# left_revision0_6.net
KiCad netlist of a schematic drawn in EAGLE
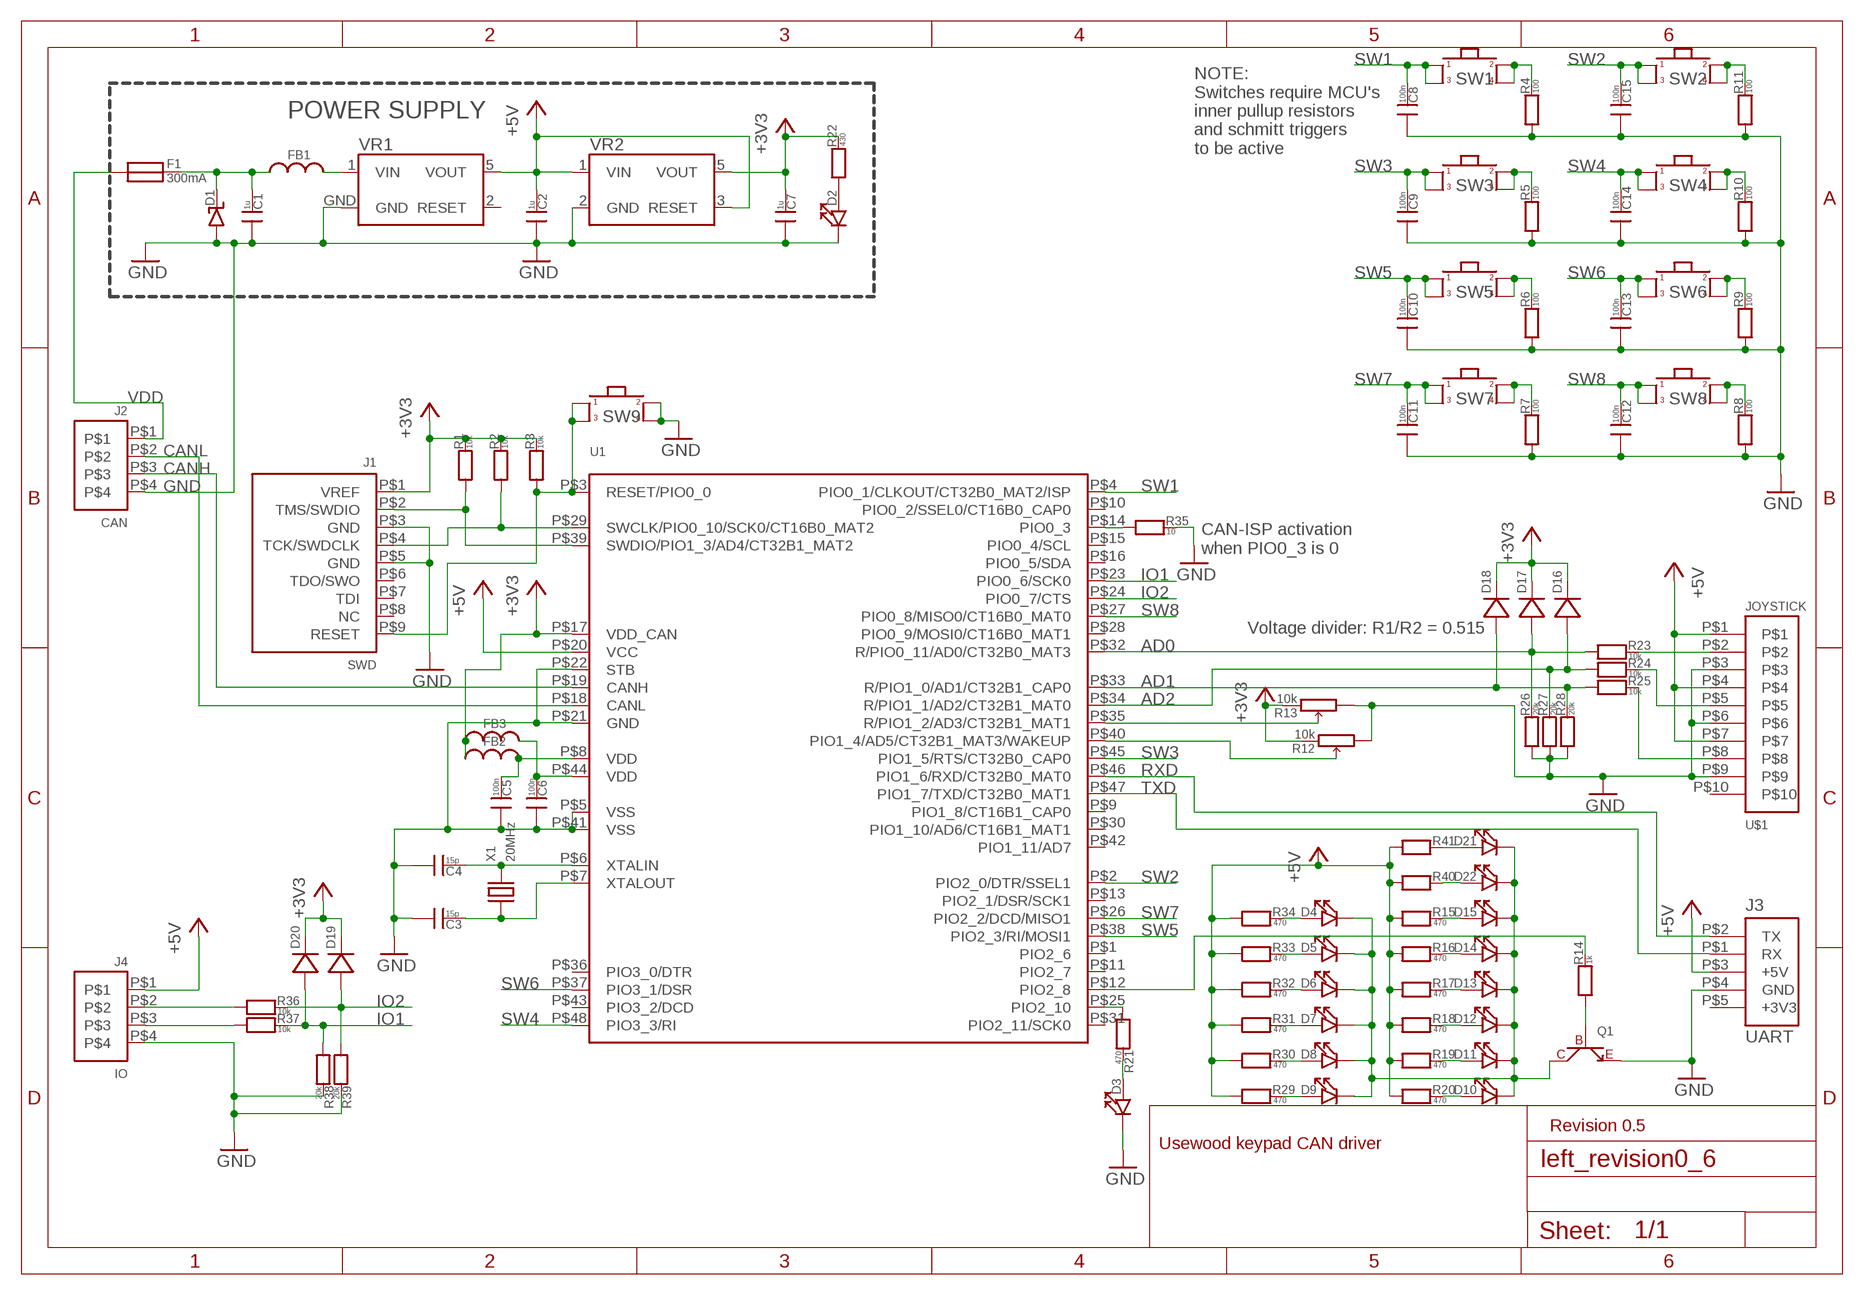
[diagram p0: schematic, sheet 1]

(export (version "E")
  (design (tool "Eeschema 10.0.6"))
  (components
    (comp (ref "C1")
      (value "1u")
      (footprint "eagle-import:0603")
      (libsource (lib "eagle-import") (part "CAP0603"))
    )
    (comp (ref "C2")
      (value "1u")
      (footprint "eagle-import:0603")
      (libsource (lib "eagle-import") (part "CAP0603"))
    )
    (comp (ref "C3")
      (value "15p")
      (footprint "eagle-import:0603")
      (libsource (lib "eagle-import") (part "CAP0603"))
    )
    (comp (ref "C4")
      (value "15p")
      (footprint "eagle-import:0603")
      (libsource (lib "eagle-import") (part "CAP0603"))
    )
    (comp (ref "C5")
      (value "100n")
      (footprint "eagle-import:0603")
      (libsource (lib "eagle-import") (part "CAP0603"))
    )
    (comp (ref "C6")
      (value "100n")
      (footprint "eagle-import:0603")
      (libsource (lib "eagle-import") (part "CAP0603"))
    )
    (comp (ref "C7")
      (value "1u")
      (footprint "eagle-import:0603")
      (libsource (lib "eagle-import") (part "CAP0603"))
    )
    (comp (ref "C8")
      (value "100n")
      (footprint "eagle-import:0603")
      (libsource (lib "eagle-import") (part "CAP0603"))
    )
    (comp (ref "C9")
      (value "100n")
      (footprint "eagle-import:0603")
      (libsource (lib "eagle-import") (part "CAP0603"))
    )
    (comp (ref "C10")
      (value "100n")
      (footprint "eagle-import:0603")
      (libsource (lib "eagle-import") (part "CAP0603"))
    )
    (comp (ref "C11")
      (value "100n")
      (footprint "eagle-import:0603")
      (libsource (lib "eagle-import") (part "CAP0603"))
    )
    (comp (ref "C12")
      (value "100n")
      (footprint "eagle-import:0603")
      (libsource (lib "eagle-import") (part "CAP0603"))
    )
    (comp (ref "C13")
      (value "100n")
      (footprint "eagle-import:0603")
      (libsource (lib "eagle-import") (part "CAP0603"))
    )
    (comp (ref "C14")
      (value "100n")
      (footprint "eagle-import:0603")
      (libsource (lib "eagle-import") (part "CAP0603"))
    )
    (comp (ref "C15")
      (value "100n")
      (footprint "eagle-import:0603")
      (libsource (lib "eagle-import") (part "CAP0603"))
    )
    (comp (ref "D1")
      (value "DIODE_TVSDO-214AA")
      (footprint "eagle-import:DO-214AB")
      (libsource (lib "eagle-import") (part "DIODE_TVSDO-214AA"))
    )
    (comp (ref "D2")
      (value "LED0603")
      (footprint "eagle-import:0603")
      (libsource (lib "eagle-import") (part "LED0603"))
    )
    (comp (ref "D3")
      (value "LED0603")
      (footprint "eagle-import:0603")
      (libsource (lib "eagle-import") (part "LED0603"))
    )
    (comp (ref "D4")
      (value "LED0603")
      (footprint "eagle-import:0603")
      (libsource (lib "eagle-import") (part "LED0603"))
    )
    (comp (ref "D5")
      (value "LED0603")
      (footprint "eagle-import:0603")
      (libsource (lib "eagle-import") (part "LED0603"))
    )
    (comp (ref "D6")
      (value "LED0603")
      (footprint "eagle-import:0603")
      (libsource (lib "eagle-import") (part "LED0603"))
    )
    (comp (ref "D7")
      (value "LED0603")
      (footprint "eagle-import:0603")
      (libsource (lib "eagle-import") (part "LED0603"))
    )
    (comp (ref "D8")
      (value "LED0603")
      (footprint "eagle-import:0603")
      (libsource (lib "eagle-import") (part "LED0603"))
    )
    (comp (ref "D9")
      (value "LED0603")
      (footprint "eagle-import:0603")
      (libsource (lib "eagle-import") (part "LED0603"))
    )
    (comp (ref "D10")
      (value "LED0603")
      (footprint "eagle-import:0603")
      (libsource (lib "eagle-import") (part "LED0603"))
    )
    (comp (ref "D11")
      (value "LED0603")
      (footprint "eagle-import:0603")
      (libsource (lib "eagle-import") (part "LED0603"))
    )
    (comp (ref "D12")
      (value "LED0603")
      (footprint "eagle-import:0603")
      (libsource (lib "eagle-import") (part "LED0603"))
    )
    (comp (ref "D13")
      (value "LED0603")
      (footprint "eagle-import:0603")
      (libsource (lib "eagle-import") (part "LED0603"))
    )
    (comp (ref "D14")
      (value "LED0603")
      (footprint "eagle-import:0603")
      (libsource (lib "eagle-import") (part "LED0603"))
    )
    (comp (ref "D15")
      (value "LED0603")
      (footprint "eagle-import:0603")
      (libsource (lib "eagle-import") (part "LED0603"))
    )
    (comp (ref "D16")
      (value "DIODEDO219AB")
      (footprint "eagle-import:DO219AB")
      (libsource (lib "eagle-import") (part "DIODEDO219AB"))
    )
    (comp (ref "D17")
      (value "DIODEDO219AB")
      (footprint "eagle-import:DO219AB")
      (libsource (lib "eagle-import") (part "DIODEDO219AB"))
    )
    (comp (ref "D18")
      (value "DIODEDO219AB")
      (footprint "eagle-import:DO219AB")
      (libsource (lib "eagle-import") (part "DIODEDO219AB"))
    )
    (comp (ref "D19")
      (value "DIODEDO219AB")
      (footprint "eagle-import:DO219AB")
      (libsource (lib "eagle-import") (part "DIODEDO219AB"))
    )
    (comp (ref "D20")
      (value "DIODEDO219AB")
      (footprint "eagle-import:DO219AB")
      (libsource (lib "eagle-import") (part "DIODEDO219AB"))
    )
    (comp (ref "D21")
      (value "LED0603")
      (footprint "eagle-import:0603")
      (libsource (lib "eagle-import") (part "LED0603"))
    )
    (comp (ref "D22")
      (value "LED0603")
      (footprint "eagle-import:0603")
      (libsource (lib "eagle-import") (part "LED0603"))
    )
    (comp (ref "F1")
      (value "300mA")
      (footprint "eagle-import:FUSE_100MA")
      (libsource (lib "eagle-import") (part "FUSE100MA"))
    )
    (comp (ref "FB1")
      (value "FERRITE0603")
      (footprint "eagle-import:0603")
      (libsource (lib "eagle-import") (part "FERRITE0603"))
    )
    (comp (ref "FB2")
      (value "FERRITE0603")
      (footprint "eagle-import:0603")
      (libsource (lib "eagle-import") (part "FERRITE0603"))
    )
    (comp (ref "FB3")
      (value "FERRITE0603")
      (footprint "eagle-import:0603")
      (libsource (lib "eagle-import") (part "FERRITE0603"))
    )
    (comp (ref "J1")
      (value "SWD")
      (footprint "eagle-import:ARM_10_PIN_JTAG_SWD_CONNECTOR")
      (libsource (lib "eagle-import") (part "ARM_JTAG/SWD_HEADER_10_PINSMD"))
    )
    (comp (ref "J2")
      (value "CAN")
      (footprint "eagle-import:MOLEX_MICRO-FIT_4WAY")
      (libsource (lib "eagle-import") (part "MOLEX_MICRO-FIT_4WAYTH"))
    )
    (comp (ref "J3")
      (value "UART")
      (footprint "eagle-import:HEADER5_1")
      (libsource (lib "eagle-import") (part "HEADER_USARTTH"))
    )
    (comp (ref "J4")
      (value "IO")
      (footprint "eagle-import:MOLEX_MICRO-FIT_4WAY")
      (libsource (lib "eagle-import") (part "MOLEX_MICRO-FIT_4WAYTH"))
    )
    (comp (ref "Q1")
      (value "NPN_TRANSISTORSOT323")
      (footprint "eagle-import:SOT323")
      (libsource (lib "eagle-import") (part "NPN_TRANSISTORSOT323"))
    )
    (comp (ref "R1")
      (value "10k")
      (footprint "eagle-import:0603")
      (libsource (lib "eagle-import") (part "RES0603"))
    )
    (comp (ref "R2")
      (value "10k")
      (footprint "eagle-import:0603")
      (libsource (lib "eagle-import") (part "RES0603"))
    )
    (comp (ref "R3")
      (value "10k")
      (footprint "eagle-import:0603")
      (libsource (lib "eagle-import") (part "RES0603"))
    )
    (comp (ref "R4")
      (value "100")
      (footprint "eagle-import:0603")
      (libsource (lib "eagle-import") (part "RES0603"))
    )
    (comp (ref "R5")
      (value "100")
      (footprint "eagle-import:0603")
      (libsource (lib "eagle-import") (part "RES0603"))
    )
    (comp (ref "R6")
      (value "100")
      (footprint "eagle-import:0603")
      (libsource (lib "eagle-import") (part "RES0603"))
    )
    (comp (ref "R7")
      (value "100")
      (footprint "eagle-import:0603")
      (libsource (lib "eagle-import") (part "RES0603"))
    )
    (comp (ref "R8")
      (value "100")
      (footprint "eagle-import:0603")
      (libsource (lib "eagle-import") (part "RES0603"))
    )
    (comp (ref "R9")
      (value "100")
      (footprint "eagle-import:0603")
      (libsource (lib "eagle-import") (part "RES0603"))
    )
    (comp (ref "R10")
      (value "100")
      (footprint "eagle-import:0603")
      (libsource (lib "eagle-import") (part "RES0603"))
    )
    (comp (ref "R11")
      (value "100")
      (footprint "eagle-import:0603")
      (libsource (lib "eagle-import") (part "RES0603"))
    )
    (comp (ref "R12")
      (value "10k")
      (footprint "eagle-import:RES_POT_RK09K1130C94")
      (libsource (lib "eagle-import") (part "RES_POTRK09K1130C94"))
    )
    (comp (ref "R13")
      (value "10k")
      (footprint "eagle-import:RES_POT_RK09K1130C94")
      (libsource (lib "eagle-import") (part "RES_POTRK09K1130C94"))
    )
    (comp (ref "R14")
      (value "1k")
      (footprint "eagle-import:0603")
      (libsource (lib "eagle-import") (part "RES0603"))
    )
    (comp (ref "R15")
      (value "470")
      (footprint "eagle-import:0603")
      (libsource (lib "eagle-import") (part "RES0603"))
    )
    (comp (ref "R16")
      (value "470")
      (footprint "eagle-import:0603")
      (libsource (lib "eagle-import") (part "RES0603"))
    )
    (comp (ref "R17")
      (value "470")
      (footprint "eagle-import:0603")
      (libsource (lib "eagle-import") (part "RES0603"))
    )
    (comp (ref "R18")
      (value "470")
      (footprint "eagle-import:0603")
      (libsource (lib "eagle-import") (part "RES0603"))
    )
    (comp (ref "R19")
      (value "470")
      (footprint "eagle-import:0603")
      (libsource (lib "eagle-import") (part "RES0603"))
    )
    (comp (ref "R20")
      (value "470")
      (footprint "eagle-import:0603")
      (libsource (lib "eagle-import") (part "RES0603"))
    )
    (comp (ref "R21")
      (value "470")
      (footprint "eagle-import:0603")
      (libsource (lib "eagle-import") (part "RES0603"))
    )
    (comp (ref "R22")
      (value "430")
      (footprint "eagle-import:0603")
      (libsource (lib "eagle-import") (part "RES0603"))
    )
    (comp (ref "R23")
      (value "10k")
      (footprint "eagle-import:0603")
      (libsource (lib "eagle-import") (part "RES0603"))
    )
    (comp (ref "R24")
      (value "10k")
      (footprint "eagle-import:0603")
      (libsource (lib "eagle-import") (part "RES0603"))
    )
    (comp (ref "R25")
      (value "10k")
      (footprint "eagle-import:0603")
      (libsource (lib "eagle-import") (part "RES0603"))
    )
    (comp (ref "R26")
      (value "20k")
      (footprint "eagle-import:0603")
      (libsource (lib "eagle-import") (part "RES0603"))
    )
    (comp (ref "R27")
      (value "20k")
      (footprint "eagle-import:0603")
      (libsource (lib "eagle-import") (part "RES0603"))
    )
    (comp (ref "R28")
      (value "20k")
      (footprint "eagle-import:0603")
      (libsource (lib "eagle-import") (part "RES0603"))
    )
    (comp (ref "R29")
      (value "470")
      (footprint "eagle-import:0603")
      (libsource (lib "eagle-import") (part "RES0603"))
    )
    (comp (ref "R30")
      (value "470")
      (footprint "eagle-import:0603")
      (libsource (lib "eagle-import") (part "RES0603"))
    )
    (comp (ref "R31")
      (value "470")
      (footprint "eagle-import:0603")
      (libsource (lib "eagle-import") (part "RES0603"))
    )
    (comp (ref "R32")
      (value "470")
      (footprint "eagle-import:0603")
      (libsource (lib "eagle-import") (part "RES0603"))
    )
    (comp (ref "R33")
      (value "470")
      (footprint "eagle-import:0603")
      (libsource (lib "eagle-import") (part "RES0603"))
    )
    (comp (ref "R34")
      (value "470")
      (footprint "eagle-import:0603")
      (libsource (lib "eagle-import") (part "RES0603"))
    )
    (comp (ref "R35")
      (value "10")
      (footprint "eagle-import:0603")
      (libsource (lib "eagle-import") (part "RES0603"))
    )
    (comp (ref "R36")
      (value "10k")
      (footprint "eagle-import:0603")
      (libsource (lib "eagle-import") (part "RES0603"))
    )
    (comp (ref "R37")
      (value "10k")
      (footprint "eagle-import:0603")
      (libsource (lib "eagle-import") (part "RES0603"))
    )
    (comp (ref "R38")
      (value "20k")
      (footprint "eagle-import:0603")
      (libsource (lib "eagle-import") (part "RES0603"))
    )
    (comp (ref "R39")
      (value "20k")
      (footprint "eagle-import:0603")
      (libsource (lib "eagle-import") (part "RES0603"))
    )
    (comp (ref "R40")
      (value "RES0603")
      (footprint "eagle-import:0603")
      (libsource (lib "eagle-import") (part "RES0603"))
    )
    (comp (ref "R41")
      (value "RES0603")
      (footprint "eagle-import:0603")
      (libsource (lib "eagle-import") (part "RES0603"))
    )
    (comp (ref "SW1")
      (value "SWITCH12X12MM_CENTER_HOLE")
      (footprint "eagle-import:SWITCH_12X12MM_CENTER_HOLE")
      (libsource (lib "eagle-import") (part "SWITCH12X12MM_CENTER_HOLE"))
    )
    (comp (ref "SW2")
      (value "SWITCH12X12MM_CENTER_HOLE")
      (footprint "eagle-import:SWITCH_12X12MM_CENTER_HOLE")
      (libsource (lib "eagle-import") (part "SWITCH12X12MM_CENTER_HOLE"))
    )
    (comp (ref "SW3")
      (value "SWITCH12X12MM_CENTER_HOLE")
      (footprint "eagle-import:SWITCH_12X12MM_CENTER_HOLE")
      (libsource (lib "eagle-import") (part "SWITCH12X12MM_CENTER_HOLE"))
    )
    (comp (ref "SW4")
      (value "SWITCH12X12MM_CENTER_HOLE")
      (footprint "eagle-import:SWITCH_12X12MM_CENTER_HOLE")
      (libsource (lib "eagle-import") (part "SWITCH12X12MM_CENTER_HOLE"))
    )
    (comp (ref "SW5")
      (value "SWITCH12X12MM_CENTER_HOLE")
      (footprint "eagle-import:SWITCH_12X12MM_CENTER_HOLE")
      (libsource (lib "eagle-import") (part "SWITCH12X12MM_CENTER_HOLE"))
    )
    (comp (ref "SW6")
      (value "SWITCH12X12MM_CENTER_HOLE")
      (footprint "eagle-import:SWITCH_12X12MM_CENTER_HOLE")
      (libsource (lib "eagle-import") (part "SWITCH12X12MM_CENTER_HOLE"))
    )
    (comp (ref "SW7")
      (value "SWITCH12X12MM_CENTER_HOLE")
      (footprint "eagle-import:SWITCH_12X12MM_CENTER_HOLE")
      (libsource (lib "eagle-import") (part "SWITCH12X12MM_CENTER_HOLE"))
    )
    (comp (ref "SW8")
      (value "SWITCH12X12MM_CENTER_HOLE")
      (footprint "eagle-import:SWITCH_12X12MM_CENTER_HOLE")
      (libsource (lib "eagle-import") (part "SWITCH12X12MM_CENTER_HOLE"))
    )
    (comp (ref "SW9")
      (value "SWITCHREGULAR")
      (footprint "eagle-import:SWITCH_REGULAR")
      (libsource (lib "eagle-import") (part "SWITCHREGULAR"))
    )
    (comp (ref "U$1")
      (value "JOYSTICK")
      (footprint "eagle-import:MOLEX-MICRO-FIT_10WAY")
      (libsource (lib "eagle-import") (part "MOLEX_MICRO-FIT_10WAYTH"))
    )
    (comp (ref "U1")
      (value "LPC11C22QFP48")
      (footprint "eagle-import:QFP48")
      (libsource (lib "eagle-import") (part "LPC11C22QFP48"))
    )
    (comp (ref "VR1")
      (value "NCV8675175AA")
      (footprint "eagle-import:175AA")
      (libsource (lib "eagle-import") (part "NCV8675175AA"))
    )
    (comp (ref "VR2")
      (value "LP2985SOP5")
      (footprint "eagle-import:SOP5")
      (libsource (lib "eagle-import") (part "LP2985SOP5"))
    )
    (comp (ref "X1")
      (value "20MHz")
      (footprint "eagle-import:XTAL_SMD_5X3.2")
      (libsource (lib "eagle-import") (part "XTALSMD_5X3.2"))
    )
  )
  (nets
    (net (code "1") (name "+3V3") (class "Default")
      (node (ref "C7") (pin "1") (pinfunction "P$2_1") (pintype "bidirectional"))
      (node (ref "D16") (pin "P$2") (pinfunction "N_P$2") (pintype "bidirectional"))
      (node (ref "D17") (pin "P$2") (pinfunction "N_P$2") (pintype "bidirectional"))
      (node (ref "D18") (pin "P$2") (pinfunction "N_P$2") (pintype "bidirectional"))
      (node (ref "D19") (pin "P$2") (pinfunction "N_P$2") (pintype "bidirectional"))
      (node (ref "D20") (pin "P$2") (pinfunction "N_P$2") (pintype "bidirectional"))
      (node (ref "FB2") (pin "0") (pinfunction "P$1_0") (pintype "bidirectional"))
      (node (ref "FB3") (pin "0") (pinfunction "P$1_0") (pintype "bidirectional"))
      (node (ref "J1") (pin "P$1") (pinfunction "VREF_P$1") (pintype "bidirectional"))
      (node (ref "R1") (pin "1") (pinfunction "P$2_1") (pintype "bidirectional"))
      (node (ref "R12") (pin "P$3") (pinfunction "P$2_P$3") (pintype "bidirectional"))
      (node (ref "R13") (pin "P$3") (pinfunction "P$2_P$3") (pintype "bidirectional"))
      (node (ref "R2") (pin "1") (pinfunction "P$2_1") (pintype "bidirectional"))
      (node (ref "R22") (pin "1") (pinfunction "P$2_1") (pintype "bidirectional"))
      (node (ref "R3") (pin "1") (pinfunction "P$2_1") (pintype "bidirectional"))
      (node (ref "U1") (pin "P$17") (pinfunction "VDD_CAN_P$17") (pintype "bidirectional"))
      (node (ref "VR2") (pin "5") (pinfunction "VOUT_5") (pintype "bidirectional"))
    )
    (net (code "2") (name "+5V") (class "Default")
      (node (ref "C2") (pin "1") (pinfunction "P$2_1") (pintype "bidirectional"))
      (node (ref "J3") (pin "P$3") (pinfunction "+5V_P$3") (pintype "bidirectional"))
      (node (ref "J4") (pin "P$1") (pinfunction "P$1_P$1") (pintype "bidirectional"))
      (node (ref "R15") (pin "0") (pinfunction "P$1_0") (pintype "bidirectional"))
      (node (ref "R16") (pin "0") (pinfunction "P$1_0") (pintype "bidirectional"))
      (node (ref "R17") (pin "0") (pinfunction "P$1_0") (pintype "bidirectional"))
      (node (ref "R18") (pin "0") (pinfunction "P$1_0") (pintype "bidirectional"))
      (node (ref "R19") (pin "0") (pinfunction "P$1_0") (pintype "bidirectional"))
      (node (ref "R20") (pin "0") (pinfunction "P$1_0") (pintype "bidirectional"))
      (node (ref "R29") (pin "0") (pinfunction "P$1_0") (pintype "bidirectional"))
      (node (ref "R30") (pin "0") (pinfunction "P$1_0") (pintype "bidirectional"))
      (node (ref "R31") (pin "0") (pinfunction "P$1_0") (pintype "bidirectional"))
      (node (ref "R32") (pin "0") (pinfunction "P$1_0") (pintype "bidirectional"))
      (node (ref "R33") (pin "0") (pinfunction "P$1_0") (pintype "bidirectional"))
      (node (ref "R34") (pin "0") (pinfunction "P$1_0") (pintype "bidirectional"))
      (node (ref "R40") (pin "0") (pinfunction "P$1_0") (pintype "bidirectional"))
      (node (ref "R41") (pin "0") (pinfunction "P$1_0") (pintype "bidirectional"))
      (node (ref "U$1") (pin "P$1") (pinfunction "P$1_P$1") (pintype "bidirectional"))
      (node (ref "U$1") (pin "P$4") (pinfunction "P$4_P$4") (pintype "bidirectional"))
      (node (ref "U$1") (pin "P$7") (pinfunction "P$7_P$7") (pintype "bidirectional"))
      (node (ref "U1") (pin "P$20") (pinfunction "VCC_P$20") (pintype "bidirectional"))
      (node (ref "VR1") (pin "5") (pinfunction "VOUT_5") (pintype "bidirectional"))
      (node (ref "VR2") (pin "1") (pinfunction "VIN_1") (pintype "bidirectional"))
      (node (ref "VR2") (pin "3") (pinfunction "RESET_3") (pintype "bidirectional"))
    )
    (net (code "3") (name "/AD0") (class "Default")
      (node (ref "D17") (pin "P$1") (pinfunction "P_P$1") (pintype "bidirectional"))
      (node (ref "R23") (pin "0") (pinfunction "P$1_0") (pintype "bidirectional"))
      (node (ref "R26") (pin "1") (pinfunction "P$2_1") (pintype "bidirectional"))
      (node (ref "U1") (pin "P$32") (pinfunction "R/PIO0_11/AD0/CT32B0_MAT3_P$32") (pintype "bidirectional"))
    )
    (net (code "4") (name "/AD1") (class "Default")
      (node (ref "D18") (pin "P$1") (pinfunction "P_P$1") (pintype "bidirectional"))
      (node (ref "R25") (pin "0") (pinfunction "P$1_0") (pintype "bidirectional"))
      (node (ref "R28") (pin "1") (pinfunction "P$2_1") (pintype "bidirectional"))
      (node (ref "U1") (pin "P$33") (pinfunction "R/PIO1_0/AD1/CT32B1_CAP0_P$33") (pintype "bidirectional"))
    )
    (net (code "5") (name "/AD2") (class "Default")
      (node (ref "D16") (pin "P$1") (pinfunction "P_P$1") (pintype "bidirectional"))
      (node (ref "R24") (pin "0") (pinfunction "P$1_0") (pintype "bidirectional"))
      (node (ref "R27") (pin "1") (pinfunction "P$2_1") (pintype "bidirectional"))
      (node (ref "U1") (pin "P$34") (pinfunction "R/PIO1_1/AD2/CT32B1_MAT0_P$34") (pintype "bidirectional"))
    )
    (net (code "6") (name "/CANH") (class "Default")
      (node (ref "J2") (pin "P$3") (pinfunction "P$3_P$3") (pintype "bidirectional"))
      (node (ref "U1") (pin "P$19") (pinfunction "CANH_P$19") (pintype "bidirectional"))
    )
    (net (code "7") (name "/CANL") (class "Default")
      (node (ref "J2") (pin "P$2") (pinfunction "P$2_P$2") (pintype "bidirectional"))
      (node (ref "U1") (pin "P$18") (pinfunction "CANL_P$18") (pintype "bidirectional"))
    )
    (net (code "8") (name "/IO1") (class "Default")
      (node (ref "D20") (pin "P$1") (pinfunction "P_P$1") (pintype "bidirectional"))
      (node (ref "R37") (pin "1") (pinfunction "P$2_1") (pintype "bidirectional"))
      (node (ref "R38") (pin "0") (pinfunction "P$1_0") (pintype "bidirectional"))
      (node (ref "U1") (pin "P$23") (pinfunction "PIO0_6/SCK0_P$23") (pintype "bidirectional"))
    )
    (net (code "9") (name "/IO2") (class "Default")
      (node (ref "D19") (pin "P$1") (pinfunction "P_P$1") (pintype "bidirectional"))
      (node (ref "R36") (pin "1") (pinfunction "P$2_1") (pintype "bidirectional"))
      (node (ref "R39") (pin "0") (pinfunction "P$1_0") (pintype "bidirectional"))
      (node (ref "U1") (pin "P$24") (pinfunction "PIO0_7/CTS_P$24") (pintype "bidirectional"))
    )
    (net (code "10") (name "/RXD") (class "Default")
      (node (ref "J3") (pin "P$2") (pinfunction "TX_P$2") (pintype "bidirectional"))
      (node (ref "U1") (pin "P$46") (pinfunction "PIO1_6/RXD/CT32B0_MAT0_P$46") (pintype "bidirectional"))
    )
    (net (code "11") (name "/SW1") (class "Default")
      (node (ref "C8") (pin "1") (pinfunction "P$2_1") (pintype "bidirectional"))
      (node (ref "SW1") (pin "P$1") (pinfunction "P$1_P$1") (pintype "bidirectional"))
      (node (ref "SW1") (pin "P$2") (pinfunction "P$3_P$2") (pintype "bidirectional"))
      (node (ref "U1") (pin "P$4") (pinfunction "PIO0_1/CLKOUT/CT32B0_MAT2/ISP_P$4") (pintype "bidirectional"))
    )
    (net (code "12") (name "/SW2") (class "Default")
      (node (ref "C15") (pin "1") (pinfunction "P$2_1") (pintype "bidirectional"))
      (node (ref "SW2") (pin "P$1") (pinfunction "P$1_P$1") (pintype "bidirectional"))
      (node (ref "SW2") (pin "P$2") (pinfunction "P$3_P$2") (pintype "bidirectional"))
      (node (ref "U1") (pin "P$2") (pinfunction "PIO2_0/DTR/SSEL1_P$2") (pintype "bidirectional"))
    )
    (net (code "13") (name "/SW3") (class "Default")
      (node (ref "C9") (pin "1") (pinfunction "P$2_1") (pintype "bidirectional"))
      (node (ref "SW3") (pin "P$1") (pinfunction "P$1_P$1") (pintype "bidirectional"))
      (node (ref "SW3") (pin "P$2") (pinfunction "P$3_P$2") (pintype "bidirectional"))
      (node (ref "U1") (pin "P$45") (pinfunction "PIO1_5/RTS/CT32B0_CAP0_P$45") (pintype "bidirectional"))
    )
    (net (code "14") (name "/SW4") (class "Default")
      (node (ref "C14") (pin "1") (pinfunction "P$2_1") (pintype "bidirectional"))
      (node (ref "SW4") (pin "P$1") (pinfunction "P$1_P$1") (pintype "bidirectional"))
      (node (ref "SW4") (pin "P$2") (pinfunction "P$3_P$2") (pintype "bidirectional"))
      (node (ref "U1") (pin "P$48") (pinfunction "PIO3_3/RI_P$48") (pintype "bidirectional"))
    )
    (net (code "15") (name "/SW5") (class "Default")
      (node (ref "C10") (pin "1") (pinfunction "P$2_1") (pintype "bidirectional"))
      (node (ref "SW5") (pin "P$1") (pinfunction "P$1_P$1") (pintype "bidirectional"))
      (node (ref "SW5") (pin "P$2") (pinfunction "P$3_P$2") (pintype "bidirectional"))
      (node (ref "U1") (pin "P$38") (pinfunction "PIO2_3/RI/MOSI1_P$38") (pintype "bidirectional"))
    )
    (net (code "16") (name "/SW6") (class "Default")
      (node (ref "C13") (pin "1") (pinfunction "P$2_1") (pintype "bidirectional"))
      (node (ref "SW6") (pin "P$1") (pinfunction "P$1_P$1") (pintype "bidirectional"))
      (node (ref "SW6") (pin "P$2") (pinfunction "P$3_P$2") (pintype "bidirectional"))
      (node (ref "U1") (pin "P$37") (pinfunction "PIO3_1/DSR_P$37") (pintype "bidirectional"))
    )
    (net (code "17") (name "/SW7") (class "Default")
      (node (ref "C11") (pin "1") (pinfunction "P$2_1") (pintype "bidirectional"))
      (node (ref "SW7") (pin "P$1") (pinfunction "P$1_P$1") (pintype "bidirectional"))
      (node (ref "SW7") (pin "P$2") (pinfunction "P$3_P$2") (pintype "bidirectional"))
      (node (ref "U1") (pin "P$26") (pinfunction "PIO2_2/DCD/MISO1_P$26") (pintype "bidirectional"))
    )
    (net (code "18") (name "/SW8") (class "Default")
      (node (ref "C12") (pin "1") (pinfunction "P$2_1") (pintype "bidirectional"))
      (node (ref "SW8") (pin "P$1") (pinfunction "P$1_P$1") (pintype "bidirectional"))
      (node (ref "SW8") (pin "P$2") (pinfunction "P$3_P$2") (pintype "bidirectional"))
      (node (ref "U1") (pin "P$27") (pinfunction "PIO0_8/MISO0/CT16B0_MAT0_P$27") (pintype "bidirectional"))
    )
    (net (code "19") (name "/TXD") (class "Default")
      (node (ref "J3") (pin "P$1") (pinfunction "RX_P$1") (pintype "bidirectional"))
      (node (ref "U1") (pin "P$47") (pinfunction "PIO1_7/TXD/CT32B0_MAT1_P$47") (pintype "bidirectional"))
    )
    (net (code "20") (name "/VDD") (class "Default")
      (node (ref "F1") (pin "P$1") (pinfunction "P$1_P$1") (pintype "bidirectional"))
      (node (ref "J2") (pin "P$1") (pinfunction "P$1_P$1") (pintype "bidirectional"))
    )
    (net (code "21") (name "GND") (class "Default")
      (node (ref "C1") (pin "0") (pinfunction "P$1_0") (pintype "bidirectional"))
      (node (ref "C10") (pin "0") (pinfunction "P$1_0") (pintype "bidirectional"))
      (node (ref "C11") (pin "0") (pinfunction "P$1_0") (pintype "bidirectional"))
      (node (ref "C12") (pin "0") (pinfunction "P$1_0") (pintype "bidirectional"))
      (node (ref "C13") (pin "0") (pinfunction "P$1_0") (pintype "bidirectional"))
      (node (ref "C14") (pin "0") (pinfunction "P$1_0") (pintype "bidirectional"))
      (node (ref "C15") (pin "0") (pinfunction "P$1_0") (pintype "bidirectional"))
      (node (ref "C2") (pin "0") (pinfunction "P$1_0") (pintype "bidirectional"))
      (node (ref "C3") (pin "0") (pinfunction "P$1_0") (pintype "bidirectional"))
      (node (ref "C4") (pin "0") (pinfunction "P$1_0") (pintype "bidirectional"))
      (node (ref "C5") (pin "0") (pinfunction "P$1_0") (pintype "bidirectional"))
      (node (ref "C6") (pin "0") (pinfunction "P$1_0") (pintype "bidirectional"))
      (node (ref "C7") (pin "0") (pinfunction "P$1_0") (pintype "bidirectional"))
      (node (ref "C8") (pin "0") (pinfunction "P$1_0") (pintype "bidirectional"))
      (node (ref "C9") (pin "0") (pinfunction "P$1_0") (pintype "bidirectional"))
      (node (ref "D1") (pin "P$1") (pinfunction "P_P$1") (pintype "bidirectional"))
      (node (ref "D2") (pin "1") (pinfunction "1_1") (pintype "bidirectional"))
      (node (ref "D3") (pin "1") (pinfunction "1_1") (pintype "bidirectional"))
      (node (ref "J1") (pin "P$3") (pinfunction "GND_P$3") (pintype "bidirectional"))
      (node (ref "J1") (pin "P$5") (pinfunction "GND_P$5") (pintype "bidirectional"))
      (node (ref "J2") (pin "P$4") (pinfunction "P$4_P$4") (pintype "bidirectional"))
      (node (ref "J3") (pin "P$4") (pinfunction "GND_P$4") (pintype "bidirectional"))
      (node (ref "J4") (pin "P$4") (pinfunction "P$4_P$4") (pintype "bidirectional"))
      (node (ref "Q1") (pin "R") (pinfunction "E_R") (pintype "bidirectional"))
      (node (ref "R10") (pin "0") (pinfunction "P$1_0") (pintype "bidirectional"))
      (node (ref "R11") (pin "0") (pinfunction "P$1_0") (pintype "bidirectional"))
      (node (ref "R12") (pin "P$1") (pinfunction "P$1_P$1") (pintype "bidirectional"))
      (node (ref "R13") (pin "P$1") (pinfunction "P$1_P$1") (pintype "bidirectional"))
      (node (ref "R26") (pin "0") (pinfunction "P$1_0") (pintype "bidirectional"))
      (node (ref "R27") (pin "0") (pinfunction "P$1_0") (pintype "bidirectional"))
      (node (ref "R28") (pin "0") (pinfunction "P$1_0") (pintype "bidirectional"))
      (node (ref "R35") (pin "1") (pinfunction "P$2_1") (pintype "bidirectional"))
      (node (ref "R38") (pin "1") (pinfunction "P$2_1") (pintype "bidirectional"))
      (node (ref "R39") (pin "1") (pinfunction "P$2_1") (pintype "bidirectional"))
      (node (ref "R4") (pin "0") (pinfunction "P$1_0") (pintype "bidirectional"))
      (node (ref "R5") (pin "0") (pinfunction "P$1_0") (pintype "bidirectional"))
      (node (ref "R6") (pin "0") (pinfunction "P$1_0") (pintype "bidirectional"))
      (node (ref "R7") (pin "0") (pinfunction "P$1_0") (pintype "bidirectional"))
      (node (ref "R8") (pin "0") (pinfunction "P$1_0") (pintype "bidirectional"))
      (node (ref "R9") (pin "0") (pinfunction "P$1_0") (pintype "bidirectional"))
      (node (ref "SW9") (pin "P$3") (pinfunction "P$4_P$3") (pintype "bidirectional"))
      (node (ref "SW9") (pin "P$4") (pinfunction "P$2_P$4") (pintype "bidirectional"))
      (node (ref "U$1") (pin "P$3") (pinfunction "P$3_P$3") (pintype "bidirectional"))
      (node (ref "U$1") (pin "P$6") (pinfunction "P$6_P$6") (pintype "bidirectional"))
      (node (ref "U$1") (pin "P$9") (pinfunction "P$9_P$9") (pintype "bidirectional"))
      (node (ref "U1") (pin "P$21") (pinfunction "GND_P$21") (pintype "bidirectional"))
      (node (ref "U1") (pin "P$22") (pinfunction "STB_P$22") (pintype "bidirectional"))
      (node (ref "U1") (pin "P$41") (pinfunction "VSS_P$41") (pintype "bidirectional"))
      (node (ref "U1") (pin "P$5") (pinfunction "VSS_P$5") (pintype "bidirectional"))
      (node (ref "VR1") (pin "GND") (pinfunction "GND_GND") (pintype "bidirectional"))
      (node (ref "VR2") (pin "2") (pinfunction "GND_2") (pintype "bidirectional"))
    )
    (net (code "22") (name "Net-(C1-P$2)") (class "Default")
      (node (ref "C1") (pin "1") (pinfunction "P$2_1") (pintype "bidirectional"))
      (node (ref "D1") (pin "P$2") (pinfunction "N_P$2") (pintype "bidirectional"))
      (node (ref "F1") (pin "P$2") (pinfunction "P$2_P$2") (pintype "bidirectional"))
      (node (ref "FB1") (pin "0") (pinfunction "P$1_0") (pintype "bidirectional"))
    )
    (net (code "23") (name "Net-(C3-P$2)") (class "Default")
      (node (ref "C3") (pin "1") (pinfunction "P$2_1") (pintype "bidirectional"))
      (node (ref "U1") (pin "P$7") (pinfunction "XTALOUT_P$7") (pintype "bidirectional"))
      (node (ref "X1") (pin "P$1") (pinfunction "P$1_P$1") (pintype "bidirectional"))
    )
    (net (code "24") (name "Net-(C4-P$2)") (class "Default")
      (node (ref "C4") (pin "1") (pinfunction "P$2_1") (pintype "bidirectional"))
      (node (ref "U1") (pin "P$6") (pinfunction "XTALIN_P$6") (pintype "bidirectional"))
      (node (ref "X1") (pin "P$2") (pinfunction "P$2_P$2") (pintype "bidirectional"))
    )
    (net (code "25") (name "Net-(C5-P$2)") (class "Default")
      (node (ref "C5") (pin "1") (pinfunction "P$2_1") (pintype "bidirectional"))
      (node (ref "FB2") (pin "1") (pinfunction "P$2_1") (pintype "bidirectional"))
      (node (ref "U1") (pin "P$8") (pinfunction "VDD_P$8") (pintype "bidirectional"))
    )
    (net (code "26") (name "Net-(C6-P$2)") (class "Default")
      (node (ref "C6") (pin "1") (pinfunction "P$2_1") (pintype "bidirectional"))
      (node (ref "FB3") (pin "1") (pinfunction "P$2_1") (pintype "bidirectional"))
      (node (ref "U1") (pin "P$44") (pinfunction "VDD_P$44") (pintype "bidirectional"))
    )
    (net (code "27") (name "Net-(FB1-P$2)") (class "Default")
      (node (ref "FB1") (pin "1") (pinfunction "P$2_1") (pintype "bidirectional"))
      (node (ref "VR1") (pin "1") (pinfunction "VIN_1") (pintype "bidirectional"))
    )
    (net (code "28") (name "Net-(J1-RESET)") (class "Default")
      (node (ref "J1") (pin "P$9") (pinfunction "RESET_P$9") (pintype "bidirectional"))
      (node (ref "R3") (pin "0") (pinfunction "P$1_0") (pintype "bidirectional"))
      (node (ref "SW9") (pin "P$1") (pinfunction "P$1_P$1") (pintype "bidirectional"))
      (node (ref "SW9") (pin "P$2") (pinfunction "P$3_P$2") (pintype "bidirectional"))
      (node (ref "U1") (pin "P$3") (pinfunction "RESET/PIO0_0_P$3") (pintype "bidirectional"))
    )
    (net (code "29") (name "Net-(J1-TCK{slash}SWDCLK)") (class "Default")
      (node (ref "J1") (pin "P$4") (pinfunction "TCK/SWDCLK_P$4") (pintype "bidirectional"))
      (node (ref "R2") (pin "0") (pinfunction "P$1_0") (pintype "bidirectional"))
      (node (ref "U1") (pin "P$29") (pinfunction "SWCLK/PIO0_10/SCK0/CT16B0_MAT2_P$29") (pintype "bidirectional"))
    )
    (net (code "30") (name "Net-(J1-TMS{slash}SWDIO)") (class "Default")
      (node (ref "J1") (pin "P$2") (pinfunction "TMS/SWDIO_P$2") (pintype "bidirectional"))
      (node (ref "R1") (pin "0") (pinfunction "P$1_0") (pintype "bidirectional"))
      (node (ref "U1") (pin "P$39") (pinfunction "SWDIO/PIO1_3/AD4/CT32B1_MAT2_P$39") (pintype "bidirectional"))
    )
    (net (code "31") (name "Net-(Q1-B)") (class "Default")
      (node (ref "Q1") (pin "L") (pinfunction "B_L") (pintype "bidirectional"))
      (node (ref "R14") (pin "0") (pinfunction "P$1_0") (pintype "bidirectional"))
    )
    (net (code "32") (name "Net-(Q1-C)") (class "Default")
      (node (ref "D10") (pin "1") (pinfunction "1_1") (pintype "bidirectional"))
      (node (ref "D11") (pin "1") (pinfunction "1_1") (pintype "bidirectional"))
      (node (ref "D12") (pin "1") (pinfunction "1_1") (pintype "bidirectional"))
      (node (ref "D13") (pin "1") (pinfunction "1_1") (pintype "bidirectional"))
      (node (ref "D14") (pin "1") (pinfunction "1_1") (pintype "bidirectional"))
      (node (ref "D15") (pin "1") (pinfunction "1_1") (pintype "bidirectional"))
      (node (ref "D21") (pin "1") (pinfunction "1_1") (pintype "bidirectional"))
      (node (ref "D22") (pin "1") (pinfunction "1_1") (pintype "bidirectional"))
      (node (ref "D4") (pin "1") (pinfunction "1_1") (pintype "bidirectional"))
      (node (ref "D5") (pin "1") (pinfunction "1_1") (pintype "bidirectional"))
      (node (ref "D6") (pin "1") (pinfunction "1_1") (pintype "bidirectional"))
      (node (ref "D7") (pin "1") (pinfunction "1_1") (pintype "bidirectional"))
      (node (ref "D8") (pin "1") (pinfunction "1_1") (pintype "bidirectional"))
      (node (ref "D9") (pin "1") (pinfunction "1_1") (pintype "bidirectional"))
      (node (ref "Q1") (pin "M") (pinfunction "C_M") (pintype "bidirectional"))
    )
    (net (code "33") (name "Net-(R4-P$2)") (class "Default")
      (node (ref "R4") (pin "1") (pinfunction "P$2_1") (pintype "bidirectional"))
      (node (ref "SW1") (pin "P$3") (pinfunction "P$2_P$3") (pintype "bidirectional"))
      (node (ref "SW1") (pin "P$4") (pinfunction "P$4_P$4") (pintype "bidirectional"))
    )
    (net (code "34") (name "Net-(R5-P$2)") (class "Default")
      (node (ref "R5") (pin "1") (pinfunction "P$2_1") (pintype "bidirectional"))
      (node (ref "SW3") (pin "P$3") (pinfunction "P$2_P$3") (pintype "bidirectional"))
      (node (ref "SW3") (pin "P$4") (pinfunction "P$4_P$4") (pintype "bidirectional"))
    )
    (net (code "35") (name "Net-(R6-P$2)") (class "Default")
      (node (ref "R6") (pin "1") (pinfunction "P$2_1") (pintype "bidirectional"))
      (node (ref "SW5") (pin "P$3") (pinfunction "P$2_P$3") (pintype "bidirectional"))
      (node (ref "SW5") (pin "P$4") (pinfunction "P$4_P$4") (pintype "bidirectional"))
    )
    (net (code "36") (name "Net-(R7-P$2)") (class "Default")
      (node (ref "R7") (pin "1") (pinfunction "P$2_1") (pintype "bidirectional"))
      (node (ref "SW7") (pin "P$3") (pinfunction "P$2_P$3") (pintype "bidirectional"))
      (node (ref "SW7") (pin "P$4") (pinfunction "P$4_P$4") (pintype "bidirectional"))
    )
    (net (code "37") (name "Net-(R8-P$2)") (class "Default")
      (node (ref "R8") (pin "1") (pinfunction "P$2_1") (pintype "bidirectional"))
      (node (ref "SW8") (pin "P$3") (pinfunction "P$2_P$3") (pintype "bidirectional"))
      (node (ref "SW8") (pin "P$4") (pinfunction "P$4_P$4") (pintype "bidirectional"))
    )
    (net (code "38") (name "Net-(R9-P$2)") (class "Default")
      (node (ref "R9") (pin "1") (pinfunction "P$2_1") (pintype "bidirectional"))
      (node (ref "SW6") (pin "P$3") (pinfunction "P$2_P$3") (pintype "bidirectional"))
      (node (ref "SW6") (pin "P$4") (pinfunction "P$4_P$4") (pintype "bidirectional"))
    )
    (net (code "39") (name "Net-(R10-P$2)") (class "Default")
      (node (ref "R10") (pin "1") (pinfunction "P$2_1") (pintype "bidirectional"))
      (node (ref "SW4") (pin "P$3") (pinfunction "P$2_P$3") (pintype "bidirectional"))
      (node (ref "SW4") (pin "P$4") (pinfunction "P$4_P$4") (pintype "bidirectional"))
    )
    (net (code "40") (name "Net-(R11-P$2)") (class "Default")
      (node (ref "R11") (pin "1") (pinfunction "P$2_1") (pintype "bidirectional"))
      (node (ref "SW2") (pin "P$3") (pinfunction "P$2_P$3") (pintype "bidirectional"))
      (node (ref "SW2") (pin "P$4") (pinfunction "P$4_P$4") (pintype "bidirectional"))
    )
    (net (code "41") (name "Net-(R12-P$3)") (class "Default")
      (node (ref "R12") (pin "P$2") (pinfunction "P$3_P$2") (pintype "bidirectional"))
      (node (ref "U1") (pin "P$40") (pinfunction "PIO1_4/AD5/CT32B1_MAT3/WAKEUP_P$40") (pintype "bidirectional"))
    )
    (net (code "42") (name "Net-(R13-P$3)") (class "Default")
      (node (ref "R13") (pin "P$2") (pinfunction "P$3_P$2") (pintype "bidirectional"))
      (node (ref "U1") (pin "P$35") (pinfunction "R/PIO1_2/AD3/CT32B1_MAT1_P$35") (pintype "bidirectional"))
    )
    (net (code "43") (name "Net-(R14-P$2)") (class "Default")
      (node (ref "R14") (pin "1") (pinfunction "P$2_1") (pintype "bidirectional"))
      (node (ref "U1") (pin "P$12") (pinfunction "PIO2_8_P$12") (pintype "bidirectional"))
    )
    (net (code "44") (name "Net-(R15-P$2)") (class "Default")
      (node (ref "D15") (pin "0") (pinfunction "0_0") (pintype "bidirectional"))
      (node (ref "R15") (pin "1") (pinfunction "P$2_1") (pintype "bidirectional"))
    )
    (net (code "45") (name "Net-(R16-P$2)") (class "Default")
      (node (ref "D14") (pin "0") (pinfunction "0_0") (pintype "bidirectional"))
      (node (ref "R16") (pin "1") (pinfunction "P$2_1") (pintype "bidirectional"))
    )
    (net (code "46") (name "Net-(R17-P$2)") (class "Default")
      (node (ref "D13") (pin "0") (pinfunction "0_0") (pintype "bidirectional"))
      (node (ref "R17") (pin "1") (pinfunction "P$2_1") (pintype "bidirectional"))
    )
    (net (code "47") (name "Net-(R18-P$2)") (class "Default")
      (node (ref "D12") (pin "0") (pinfunction "0_0") (pintype "bidirectional"))
      (node (ref "R18") (pin "1") (pinfunction "P$2_1") (pintype "bidirectional"))
    )
    (net (code "48") (name "Net-(R19-P$2)") (class "Default")
      (node (ref "D11") (pin "0") (pinfunction "0_0") (pintype "bidirectional"))
      (node (ref "R19") (pin "1") (pinfunction "P$2_1") (pintype "bidirectional"))
    )
    (net (code "49") (name "Net-(R20-P$2)") (class "Default")
      (node (ref "D10") (pin "0") (pinfunction "0_0") (pintype "bidirectional"))
      (node (ref "R20") (pin "1") (pinfunction "P$2_1") (pintype "bidirectional"))
    )
    (net (code "50") (name "Net-(R21-P$1)") (class "Default")
      (node (ref "R21") (pin "0") (pinfunction "P$1_0") (pintype "bidirectional"))
      (node (ref "U1") (pin "P$25") (pinfunction "PIO2_10_P$25") (pintype "bidirectional"))
    )
    (net (code "51") (name "Net-(R21-P$2)") (class "Default")
      (node (ref "D3") (pin "0") (pinfunction "0_0") (pintype "bidirectional"))
      (node (ref "R21") (pin "1") (pinfunction "P$2_1") (pintype "bidirectional"))
    )
    (net (code "52") (name "Net-(R22-P$1)") (class "Default")
      (node (ref "D2") (pin "0") (pinfunction "0_0") (pintype "bidirectional"))
      (node (ref "R22") (pin "0") (pinfunction "P$1_0") (pintype "bidirectional"))
    )
    (net (code "53") (name "Net-(R23-P$2)") (class "Default")
      (node (ref "R23") (pin "1") (pinfunction "P$2_1") (pintype "bidirectional"))
      (node (ref "U$1") (pin "P$2") (pinfunction "P$2_P$2") (pintype "bidirectional"))
    )
    (net (code "54") (name "Net-(R24-P$2)") (class "Default")
      (node (ref "R24") (pin "1") (pinfunction "P$2_1") (pintype "bidirectional"))
      (node (ref "U$1") (pin "P$5") (pinfunction "P$5_P$5") (pintype "bidirectional"))
    )
    (net (code "55") (name "Net-(R25-P$2)") (class "Default")
      (node (ref "R25") (pin "1") (pinfunction "P$2_1") (pintype "bidirectional"))
      (node (ref "U$1") (pin "P$8") (pinfunction "P$8_P$8") (pintype "bidirectional"))
    )
    (net (code "56") (name "Net-(R29-P$2)") (class "Default")
      (node (ref "D9") (pin "0") (pinfunction "0_0") (pintype "bidirectional"))
      (node (ref "R29") (pin "1") (pinfunction "P$2_1") (pintype "bidirectional"))
    )
    (net (code "57") (name "Net-(R30-P$2)") (class "Default")
      (node (ref "D8") (pin "0") (pinfunction "0_0") (pintype "bidirectional"))
      (node (ref "R30") (pin "1") (pinfunction "P$2_1") (pintype "bidirectional"))
    )
    (net (code "58") (name "Net-(R31-P$2)") (class "Default")
      (node (ref "D7") (pin "0") (pinfunction "0_0") (pintype "bidirectional"))
      (node (ref "R31") (pin "1") (pinfunction "P$2_1") (pintype "bidirectional"))
    )
    (net (code "59") (name "Net-(R32-P$2)") (class "Default")
      (node (ref "D6") (pin "0") (pinfunction "0_0") (pintype "bidirectional"))
      (node (ref "R32") (pin "1") (pinfunction "P$2_1") (pintype "bidirectional"))
    )
    (net (code "60") (name "Net-(R33-P$2)") (class "Default")
      (node (ref "D5") (pin "0") (pinfunction "0_0") (pintype "bidirectional"))
      (node (ref "R33") (pin "1") (pinfunction "P$2_1") (pintype "bidirectional"))
    )
    (net (code "61") (name "Net-(R34-P$2)") (class "Default")
      (node (ref "D4") (pin "0") (pinfunction "0_0") (pintype "bidirectional"))
      (node (ref "R34") (pin "1") (pinfunction "P$2_1") (pintype "bidirectional"))
    )
    (net (code "62") (name "Net-(R35-P$1)") (class "Default")
      (node (ref "R35") (pin "0") (pinfunction "P$1_0") (pintype "bidirectional"))
      (node (ref "U1") (pin "P$14") (pinfunction "PIO0_3_P$14") (pintype "bidirectional"))
    )
    (net (code "63") (name "Net-(R36-P$1)") (class "Default")
      (node (ref "J4") (pin "P$2") (pinfunction "P$2_P$2") (pintype "bidirectional"))
      (node (ref "R36") (pin "0") (pinfunction "P$1_0") (pintype "bidirectional"))
    )
    (net (code "64") (name "Net-(R37-P$1)") (class "Default")
      (node (ref "J4") (pin "P$3") (pinfunction "P$3_P$3") (pintype "bidirectional"))
      (node (ref "R37") (pin "0") (pinfunction "P$1_0") (pintype "bidirectional"))
    )
    (net (code "65") (name "Net-(R40-P$2)") (class "Default")
      (node (ref "D22") (pin "0") (pinfunction "0_0") (pintype "bidirectional"))
      (node (ref "R40") (pin "1") (pinfunction "P$2_1") (pintype "bidirectional"))
    )
    (net (code "66") (name "Net-(R41-P$2)") (class "Default")
      (node (ref "D21") (pin "0") (pinfunction "0_0") (pintype "bidirectional"))
      (node (ref "R41") (pin "1") (pinfunction "P$2_1") (pintype "bidirectional"))
    )
    (net (code "67") (name "unconnected-(J1-NC-PadP$8)") (class "Default")
      (node (ref "J1") (pin "P$8") (pinfunction "NC_P$8") (pintype "bidirectional"))
    )
    (net (code "68") (name "unconnected-(J1-TDI-PadP$7)") (class "Default")
      (node (ref "J1") (pin "P$7") (pinfunction "TDI_P$7") (pintype "bidirectional"))
    )
    (net (code "69") (name "unconnected-(J1-TDO{slash}SWO-PadP$6)") (class "Default")
      (node (ref "J1") (pin "P$6") (pinfunction "TDO/SWO_P$6") (pintype "bidirectional"))
    )
    (net (code "70") (name "unconnected-(J3-+3V3-PadP$5)") (class "Default")
      (node (ref "J3") (pin "P$5") (pinfunction "+3V3_P$5") (pintype "bidirectional"))
    )
    (net (code "71") (name "unconnected-(U$1-PadP$10)") (class "Default")
      (node (ref "U$1") (pin "P$10") (pinfunction "P$10_P$10") (pintype "bidirectional"))
    )
    (net (code "72") (name "unconnected-(U1-PIO0_2{slash}SSEL0{slash}CT16B0_CAP0-PadP$10)") (class "Default")
      (node (ref "U1") (pin "P$10") (pinfunction "PIO0_2/SSEL0/CT16B0_CAP0_P$10") (pintype "bidirectional"))
    )
    (net (code "73") (name "unconnected-(U1-PIO0_4{slash}SCL-PadP$15)") (class "Default")
      (node (ref "U1") (pin "P$15") (pinfunction "PIO0_4/SCL_P$15") (pintype "bidirectional"))
    )
    (net (code "74") (name "unconnected-(U1-PIO0_5{slash}SDA-PadP$16)") (class "Default")
      (node (ref "U1") (pin "P$16") (pinfunction "PIO0_5/SDA_P$16") (pintype "bidirectional"))
    )
    (net (code "75") (name "unconnected-(U1-PIO0_9{slash}MOSI0{slash}CT16B0_MAT1-PadP$28)") (class "Default")
      (node (ref "U1") (pin "P$28") (pinfunction "PIO0_9/MOSI0/CT16B0_MAT1_P$28") (pintype "bidirectional"))
    )
    (net (code "76") (name "unconnected-(U1-PIO1_8{slash}CT16B1_CAP0-PadP$9)") (class "Default")
      (node (ref "U1") (pin "P$9") (pinfunction "PIO1_8/CT16B1_CAP0_P$9") (pintype "bidirectional"))
    )
    (net (code "77") (name "unconnected-(U1-PIO1_10{slash}AD6{slash}CT16B1_MAT1-PadP$30)") (class "Default")
      (node (ref "U1") (pin "P$30") (pinfunction "PIO1_10/AD6/CT16B1_MAT1_P$30") (pintype "bidirectional"))
    )
    (net (code "78") (name "unconnected-(U1-PIO1_11{slash}AD7-PadP$42)") (class "Default")
      (node (ref "U1") (pin "P$42") (pinfunction "PIO1_11/AD7_P$42") (pintype "bidirectional"))
    )
    (net (code "79") (name "unconnected-(U1-PIO2_1{slash}DSR{slash}SCK1-PadP$13)") (class "Default")
      (node (ref "U1") (pin "P$13") (pinfunction "PIO2_1/DSR/SCK1_P$13") (pintype "bidirectional"))
    )
    (net (code "80") (name "unconnected-(U1-PIO2_6-PadP$1)") (class "Default")
      (node (ref "U1") (pin "P$1") (pinfunction "PIO2_6_P$1") (pintype "bidirectional"))
    )
    (net (code "81") (name "unconnected-(U1-PIO2_7-PadP$11)") (class "Default")
      (node (ref "U1") (pin "P$11") (pinfunction "PIO2_7_P$11") (pintype "bidirectional"))
    )
    (net (code "82") (name "unconnected-(U1-PIO2_11{slash}SCK0-PadP$31)") (class "Default")
      (node (ref "U1") (pin "P$31") (pinfunction "PIO2_11/SCK0_P$31") (pintype "bidirectional"))
    )
    (net (code "83") (name "unconnected-(U1-PIO3_0{slash}DTR-PadP$36)") (class "Default")
      (node (ref "U1") (pin "P$36") (pinfunction "PIO3_0/DTR_P$36") (pintype "bidirectional"))
    )
    (net (code "84") (name "unconnected-(U1-PIO3_2{slash}DCD-PadP$43)") (class "Default")
      (node (ref "U1") (pin "P$43") (pinfunction "PIO3_2/DCD_P$43") (pintype "bidirectional"))
    )
    (net (code "85") (name "unconnected-(VR1-RESET-Pad2)") (class "Default")
      (node (ref "VR1") (pin "2") (pinfunction "RESET_2") (pintype "bidirectional"))
    )
  )
)
